# ESP.net
KiCad netlist of a schematic drawn in Altium Designer
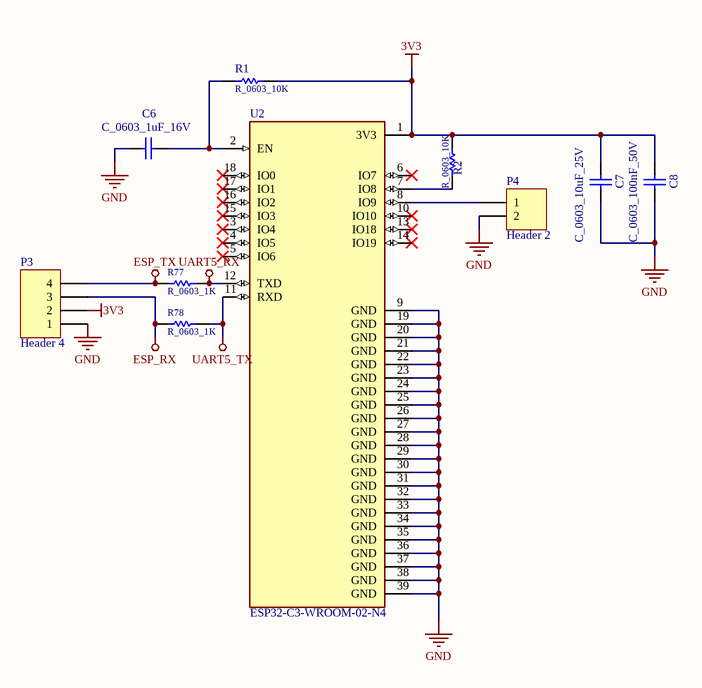
[diagram p0: ESP.SchDoc]

(export (version "E")
  (design (tool "Eeschema 10.0.6"))
  (components
    (comp (ref "C6")
      (value "C_0603_1uF_16V")
      (footprint "CAP 0603")
      (description "Capacitor")
      (fields (field (name "PUBLISHER") "Altium Limited"))
      (libsource (lib "HUE") (part "Cap"))
    )
    (comp (ref "C7")
      (value "C_0603_10uF_25V")
      (footprint "CAP 0603")
      (description "Capacitor")
      (fields (field (name "PUBLISHER") "Altium Limited"))
      (libsource (lib "HUE") (part "Cap"))
    )
    (comp (ref "C8")
      (value "C_0603_100nF_50V")
      (footprint "CAP 0603")
      (description "Capacitor")
      (fields (field (name "PUBLISHER") "Altium Limited"))
      (libsource (lib "HUE") (part "Cap"))
    )
    (comp (ref "P3")
      (value "Header 4")
      (footprint "HDR1X4")
      (description "Header, 4-Pin")
      (fields (field (name "PUBLISHER") "Altium Limited"))
      (libsource (lib "Miscellaneous Connectors") (part "Header 4"))
    )
    (comp (ref "P4")
      (value "Header 2")
      (footprint "HDR1X2")
      (description "Header, 2-Pin")
      (fields (field (name "PUBLISHER") "Altium Limited"))
      (libsource (lib "Miscellaneous Connectors") (part "Header 2"))
    )
    (comp (ref "R1")
      (value "R_0603_10K")
      (footprint "RES 0603")
      (description "Resistor")
      (fields (field (name "PUBLISHER") "Altium Limited"))
      (libsource (lib "HUE") (part "Res"))
    )
    (comp (ref "R2")
      (value "R_0603_10K")
      (footprint "RES 0603")
      (description "Resistor")
      (fields (field (name "PUBLISHER") "Altium Limited"))
      (libsource (lib "HUE") (part "Res"))
    )
    (comp (ref "R77")
      (value "R_0603_1K")
      (footprint "RES 0603")
      (description "Resistor")
      (fields (field (name "PUBLISHER") "Altium Limited"))
      (libsource (lib "HUE") (part "Res"))
    )
    (comp (ref "R78")
      (value "R_0603_1K")
      (footprint "RES 0603")
      (description "Resistor")
      (fields (field (name "PUBLISHER") "Altium Limited"))
      (libsource (lib "HUE") (part "Res"))
    )
    (comp (ref "U2")
      (value "ESP32-C3-WROOM-02-N4")
      (footprint "ESP32-C3-WROOM-02-H4")
      (fields (field (name "MF") "Espressif Systems"))
      (libsource (lib "HUE") (part "ESP32-C3-WROOM-02-N4"))
    )
  )
  (nets
    (net (code "1") (name "3V3") (class "Default")
      (node (ref "C7") (pin "2") (pinfunction "2_2") (pintype "passive"))
      (node (ref "C8") (pin "2") (pinfunction "2_2") (pintype "passive"))
      (node (ref "P3") (pin "2") (pinfunction "2_2") (pintype "passive"))
      (node (ref "R1") (pin "1") (pinfunction "1_1") (pintype "passive"))
      (node (ref "R2") (pin "1") (pinfunction "1_1") (pintype "passive"))
      (node (ref "U2") (pin "1") (pinfunction "3V3_1") (pintype "power_in"))
    )
    (net (code "2") (name "ESP_RX") (class "Default")
      (node (ref "P3") (pin "3") (pinfunction "3_3") (pintype "passive"))
      (node (ref "R78") (pin "2") (pinfunction "2_2") (pintype "passive"))
    )
    (net (code "3") (name "ESP_TX") (class "Default")
      (node (ref "P3") (pin "4") (pinfunction "4_4") (pintype "passive"))
      (node (ref "R77") (pin "2") (pinfunction "2_2") (pintype "passive"))
    )
    (net (code "4") (name "GND") (class "Default")
      (node (ref "C6") (pin "2") (pinfunction "2_2") (pintype "passive"))
      (node (ref "C7") (pin "1") (pinfunction "1_1") (pintype "passive"))
      (node (ref "C8") (pin "1") (pinfunction "1_1") (pintype "passive"))
      (node (ref "P3") (pin "1") (pinfunction "1_1") (pintype "passive"))
      (node (ref "P4") (pin "2") (pinfunction "2_2") (pintype "passive"))
      (node (ref "U2") (pin "19") (pinfunction "GND_19") (pintype "power_in"))
      (node (ref "U2") (pin "20") (pinfunction "GND_20") (pintype "power_in"))
      (node (ref "U2") (pin "21") (pinfunction "GND_21") (pintype "power_in"))
      (node (ref "U2") (pin "22") (pinfunction "GND_22") (pintype "power_in"))
      (node (ref "U2") (pin "23") (pinfunction "GND_23") (pintype "power_in"))
      (node (ref "U2") (pin "24") (pinfunction "GND_24") (pintype "power_in"))
      (node (ref "U2") (pin "25") (pinfunction "GND_25") (pintype "power_in"))
      (node (ref "U2") (pin "26") (pinfunction "GND_26") (pintype "power_in"))
      (node (ref "U2") (pin "27") (pinfunction "GND_27") (pintype "power_in"))
      (node (ref "U2") (pin "28") (pinfunction "GND_28") (pintype "power_in"))
      (node (ref "U2") (pin "29") (pinfunction "GND_29") (pintype "power_in"))
      (node (ref "U2") (pin "30") (pinfunction "GND_30") (pintype "power_in"))
      (node (ref "U2") (pin "31") (pinfunction "GND_31") (pintype "power_in"))
      (node (ref "U2") (pin "32") (pinfunction "GND_32") (pintype "power_in"))
      (node (ref "U2") (pin "33") (pinfunction "GND_33") (pintype "power_in"))
      (node (ref "U2") (pin "34") (pinfunction "GND_34") (pintype "power_in"))
      (node (ref "U2") (pin "35") (pinfunction "GND_35") (pintype "power_in"))
      (node (ref "U2") (pin "36") (pinfunction "GND_36") (pintype "power_in"))
      (node (ref "U2") (pin "37") (pinfunction "GND_37") (pintype "power_in"))
      (node (ref "U2") (pin "38") (pinfunction "GND_38") (pintype "power_in"))
      (node (ref "U2") (pin "39") (pinfunction "GND_39") (pintype "power_in"))
      (node (ref "U2") (pin "9") (pinfunction "GND_9") (pintype "power_in"))
    )
    (net (code "5") (name "Net-(U2-EN)") (class "Default")
      (node (ref "C6") (pin "1") (pinfunction "1_1") (pintype "passive"))
      (node (ref "R1") (pin "2") (pinfunction "2_2") (pintype "passive"))
      (node (ref "U2") (pin "2") (pinfunction "EN_2") (pintype "input"))
    )
    (net (code "6") (name "Net-(U2-IO8)") (class "Default")
      (node (ref "R2") (pin "2") (pinfunction "2_2") (pintype "passive"))
      (node (ref "U2") (pin "7") (pinfunction "IO8_7") (pintype "bidirectional"))
    )
    (net (code "7") (name "Net-(U2-IO9)") (class "Default")
      (node (ref "P4") (pin "1") (pinfunction "1_1") (pintype "passive"))
      (node (ref "U2") (pin "8") (pinfunction "IO9_8") (pintype "bidirectional"))
    )
    (net (code "8") (name "UART5_RX") (class "Default")
      (node (ref "R77") (pin "1") (pinfunction "1_1") (pintype "passive"))
      (node (ref "U2") (pin "12") (pinfunction "TXD_12") (pintype "bidirectional"))
    )
    (net (code "9") (name "UART5_TX") (class "Default")
      (node (ref "R78") (pin "1") (pinfunction "1_1") (pintype "passive"))
      (node (ref "U2") (pin "11") (pinfunction "RXD_11") (pintype "bidirectional"))
    )
    (net (code "10") (name "unconnected-(U2-IO0-Pad18)") (class "Default")
      (node (ref "U2") (pin "18") (pinfunction "IO0_18") (pintype "bidirectional+no_connect"))
    )
    (net (code "11") (name "unconnected-(U2-IO1-Pad17)") (class "Default")
      (node (ref "U2") (pin "17") (pinfunction "IO1_17") (pintype "bidirectional+no_connect"))
    )
    (net (code "12") (name "unconnected-(U2-IO2-Pad16)") (class "Default")
      (node (ref "U2") (pin "16") (pinfunction "IO2_16") (pintype "bidirectional+no_connect"))
    )
    (net (code "13") (name "unconnected-(U2-IO3-Pad15)") (class "Default")
      (node (ref "U2") (pin "15") (pinfunction "IO3_15") (pintype "bidirectional+no_connect"))
    )
    (net (code "14") (name "unconnected-(U2-IO4-Pad3)") (class "Default")
      (node (ref "U2") (pin "3") (pinfunction "IO4_3") (pintype "bidirectional+no_connect"))
    )
    (net (code "15") (name "unconnected-(U2-IO5-Pad4)") (class "Default")
      (node (ref "U2") (pin "4") (pinfunction "IO5_4") (pintype "bidirectional+no_connect"))
    )
    (net (code "16") (name "unconnected-(U2-IO6-Pad5)") (class "Default")
      (node (ref "U2") (pin "5") (pinfunction "IO6_5") (pintype "bidirectional+no_connect"))
    )
    (net (code "17") (name "unconnected-(U2-IO7-Pad6)") (class "Default")
      (node (ref "U2") (pin "6") (pinfunction "IO7_6") (pintype "bidirectional+no_connect"))
    )
    (net (code "18") (name "unconnected-(U2-IO10-Pad10)") (class "Default")
      (node (ref "U2") (pin "10") (pinfunction "IO10_10") (pintype "bidirectional+no_connect"))
    )
    (net (code "19") (name "unconnected-(U2-IO18-Pad13)") (class "Default")
      (node (ref "U2") (pin "13") (pinfunction "IO18_13") (pintype "bidirectional+no_connect"))
    )
    (net (code "20") (name "unconnected-(U2-IO19-Pad14)") (class "Default")
      (node (ref "U2") (pin "14") (pinfunction "IO19_14") (pintype "bidirectional+no_connect"))
    )
  )
)
